# 03_Breakout_Headers.net
KiCad netlist of a schematic drawn in Altium Designer
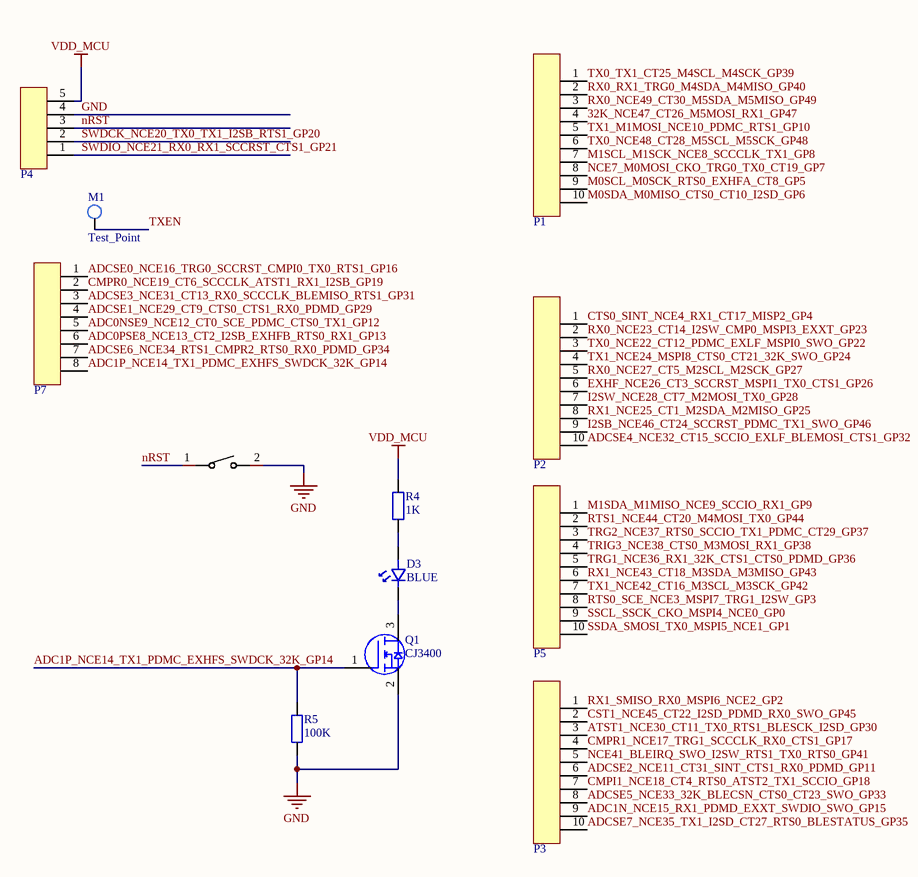
[diagram p0: [03]Breakout Headers.SchDoc]

(export (version "E")
  (design (tool "Eeschema 10.0.6"))
  (components
    (comp (ref "D3")
      (value "BLUE")
      (footprint "LEDC1608L")
      (description "Surface Mount LED")
      (libsource (lib "Discrete") (part "LED_SMD"))
    )
    (comp (ref "M1")
      (value "Test_Point")
      (footprint "MARK_Small")
      (libsource (lib "AmbiqPhoenix") (part "Test_Point_Small"))
    )
    (comp (ref "P1")
      (value "Header 1X10")
      (footprint "HEADER1X10")
      (libsource (lib "AmbiqPhoenix") (part "HDR1X10"))
    )
    (comp (ref "P2")
      (value "Header 1X10")
      (footprint "HEADER1X10")
      (libsource (lib "AmbiqPhoenix") (part "HDR1X10"))
    )
    (comp (ref "P3")
      (value "Header 1X10")
      (footprint "HEADER1X10")
      (libsource (lib "AmbiqPhoenix") (part "HDR1X10"))
    )
    (comp (ref "P4")
      (value "Header 1X8")
      (footprint "HEADER1X5")
      (libsource (lib "AmbiqPhoenix") (part "HDR1X5"))
    )
    (comp (ref "P5")
      (value "Header 1X10")
      (footprint "HEADER1X10")
      (libsource (lib "AmbiqPhoenix") (part "HDR1X10"))
    )
    (comp (ref "P7")
      (value "Header 1X8")
      (footprint "HEADER1X8")
      (libsource (lib "AmbiqPhoenix") (part "HDR1X8"))
    )
    (comp (ref "Q1")
      (value "CJ3400")
      (footprint "SOT23-3L")
      (description "N-Channel MOSFET")
      (libsource (lib "AmbiqPhoenix") (part "MOS_N"))
    )
    (comp (ref "R4")
      (value "1K")
      (footprint "RESC1005L")
      (description "Surface Mount Resistor")
      (libsource (lib "Discrete") (part "RES_CHP"))
    )
    (comp (ref "R5")
      (value "100K")
      (footprint "RESC1005L")
      (description "Surface Mount Resistor")
      (libsource (lib "Discrete") (part "RES_CHP"))
    )
    (comp (ref "SW1")
      (value "TS-1088-AR02016")
      (footprint "SW-SMD_L4.0-W2.9-LS5.0")
      (fields (field (name "MANUFACTURER") "XUNPU(讯普)"))
      (libsource (lib "AmbiqPhoenix") (part "TS-1088-AR02016"))
    )
  )
  (nets
    (net (code "1") (name "/32K_NCE47_CT26_M5MOSI_RX1_GP47") (class "Default")
      (node (ref "P1") (pin "4") (pinfunction "4_4") (pintype "passive"))
    )
    (net (code "2") (name "/ADC0NSE9_NCE12_CT0_SCE_PDMC_CTS0_TX1_GP12") (class "Default")
      (node (ref "P7") (pin "5") (pinfunction "5_5") (pintype "passive"))
    )
    (net (code "3") (name "/ADC0PSE8_NCE13_CT2_I2SB_EXHFB_RTS0_RX1_GP13") (class "Default")
      (node (ref "P7") (pin "6") (pinfunction "6_6") (pintype "passive"))
    )
    (net (code "4") (name "/ADC1N_NCE15_RX1_PDMD_EXXT_SWDIO_SWO_GP15") (class "Default")
      (node (ref "P3") (pin "9") (pinfunction "9_9") (pintype "passive"))
    )
    (net (code "5") (name "/ADC1P_NCE14_TX1_PDMC_EXHFS_SWDCK_32K_GP14") (class "Default")
      (node (ref "P7") (pin "8") (pinfunction "8_8") (pintype "passive"))
      (node (ref "Q1") (pin "1") (pinfunction "1_1") (pintype "passive"))
      (node (ref "R5") (pin "2") (pinfunction "2_2") (pintype "passive"))
    )
    (net (code "6") (name "/ADCSE0_NCE16_TRG0_SCCRST_CMPI0_TX0_RTS1_GP16") (class "Default")
      (node (ref "P7") (pin "1") (pinfunction "1_1") (pintype "passive"))
    )
    (net (code "7") (name "/ADCSE1_NCE29_CT9_CTS0_CTS1_RX0_PDMD_GP29") (class "Default")
      (node (ref "P7") (pin "4") (pinfunction "4_4") (pintype "passive"))
    )
    (net (code "8") (name "/ADCSE2_NCE11_CT31_SINT_CTS1_RX0_PDMD_GP11") (class "Default")
      (node (ref "P3") (pin "6") (pinfunction "6_6") (pintype "passive"))
    )
    (net (code "9") (name "/ADCSE3_NCE31_CT13_RX0_SCCCLK_BLEMISO_RTS1_GP31") (class "Default")
      (node (ref "P7") (pin "3") (pinfunction "3_3") (pintype "passive"))
    )
    (net (code "10") (name "/ADCSE4_NCE32_CT15_SCCIO_EXLF_BLEMOSI_CTS1_GP32") (class "Default")
      (node (ref "P2") (pin "10") (pinfunction "10_10") (pintype "passive"))
    )
    (net (code "11") (name "/ADCSE5_NCE33_32K_BLECSN_CTS0_CT23_SWO_GP33") (class "Default")
      (node (ref "P3") (pin "8") (pinfunction "8_8") (pintype "passive"))
    )
    (net (code "12") (name "/ADCSE6_NCE34_RTS1_CMPR2_RTS0_RX0_PDMD_GP34") (class "Default")
      (node (ref "P7") (pin "7") (pinfunction "7_7") (pintype "passive"))
    )
    (net (code "13") (name "/ADCSE7_NCE35_TX1_I2SD_CT27_RTS0_BLESTATUS_GP35") (class "Default")
      (node (ref "P3") (pin "10") (pinfunction "10_10") (pintype "passive"))
    )
    (net (code "14") (name "/ATST1_NCE30_CT11_TX0_RTS1_BLESCK_I2SD_GP30") (class "Default")
      (node (ref "P3") (pin "3") (pinfunction "3_3") (pintype "passive"))
    )
    (net (code "15") (name "/CMPI1_NCE18_CT4_RTS0_ATST2_TX1_SCCIO_GP18") (class "Default")
      (node (ref "P3") (pin "7") (pinfunction "7_7") (pintype "passive"))
    )
    (net (code "16") (name "/CMPR0_NCE19_CT6_SCCCLK_ATST1_RX1_I2SB_GP19") (class "Default")
      (node (ref "P7") (pin "2") (pinfunction "2_2") (pintype "passive"))
    )
    (net (code "17") (name "/CMPR1_NCE17_TRG1_SCCCLK_RX0_CTS1_GP17") (class "Default")
      (node (ref "P3") (pin "4") (pinfunction "4_4") (pintype "passive"))
    )
    (net (code "18") (name "/CST1_NCE45_CT22_I2SD_PDMD_RX0_SWO_GP45") (class "Default")
      (node (ref "P3") (pin "2") (pinfunction "2_2") (pintype "passive"))
    )
    (net (code "19") (name "/CTS0_SINT_NCE4_RX1_CT17_MISP2_GP4") (class "Default")
      (node (ref "P2") (pin "1") (pinfunction "1_1") (pintype "passive"))
    )
    (net (code "20") (name "/EXHF_NCE26_CT3_SCCRST_MSPI1_TX0_CTS1_GP26") (class "Default")
      (node (ref "P2") (pin "6") (pinfunction "6_6") (pintype "passive"))
    )
    (net (code "21") (name "/I2SB_NCE46_CT24_SCCRST_PDMC_TX1_SWO_GP46") (class "Default")
      (node (ref "P2") (pin "9") (pinfunction "9_9") (pintype "passive"))
    )
    (net (code "22") (name "/I2SW_NCE28_CT7_M2MOSI_TX0_GP28") (class "Default")
      (node (ref "P2") (pin "7") (pinfunction "7_7") (pintype "passive"))
    )
    (net (code "23") (name "/M0SCL_M0SCK_RTS0_EXHFA_CT8_GP5") (class "Default")
      (node (ref "P1") (pin "9") (pinfunction "9_9") (pintype "passive"))
    )
    (net (code "24") (name "/M0SDA_M0MISO_CTS0_CT10_I2SD_GP6") (class "Default")
      (node (ref "P1") (pin "10") (pinfunction "10_10") (pintype "passive"))
    )
    (net (code "25") (name "/M1SCL_M1SCK_NCE8_SCCCLK_TX1_GP8") (class "Default")
      (node (ref "P1") (pin "7") (pinfunction "7_7") (pintype "passive"))
    )
    (net (code "26") (name "/M1SDA_M1MISO_NCE9_SCCIO_RX1_GP9") (class "Default")
      (node (ref "P5") (pin "1") (pinfunction "1_1") (pintype "passive"))
    )
    (net (code "27") (name "/NCE7_M0MOSI_CKO_TRG0_TX0_CT19_GP7") (class "Default")
      (node (ref "P1") (pin "8") (pinfunction "8_8") (pintype "passive"))
    )
    (net (code "28") (name "/NCE41_BLEIRQ_SWO_I2SW_RTS1_TX0_RTS0_GP41") (class "Default")
      (node (ref "P3") (pin "5") (pinfunction "5_5") (pintype "passive"))
    )
    (net (code "29") (name "/RTS0_SCE_NCE3_MSPI7_TRG1_I2SW_GP3") (class "Default")
      (node (ref "P5") (pin "8") (pinfunction "8_8") (pintype "passive"))
    )
    (net (code "30") (name "/RTS1_NCE44_CT20_M4MOSI_TX0_GP44") (class "Default")
      (node (ref "P5") (pin "2") (pinfunction "2_2") (pintype "passive"))
    )
    (net (code "31") (name "/RX0_NCE23_CT14_I2SW_CMP0_MSPI3_EXXT_GP23") (class "Default")
      (node (ref "P2") (pin "2") (pinfunction "2_2") (pintype "passive"))
    )
    (net (code "32") (name "/RX0_NCE27_CT5_M2SCL_M2SCK_GP27") (class "Default")
      (node (ref "P2") (pin "5") (pinfunction "5_5") (pintype "passive"))
    )
    (net (code "33") (name "/RX0_NCE49_CT30_M5SDA_M5MISO_GP49") (class "Default")
      (node (ref "P1") (pin "3") (pinfunction "3_3") (pintype "passive"))
    )
    (net (code "34") (name "/RX0_RX1_TRG0_M4SDA_M4MISO_GP40") (class "Default")
      (node (ref "P1") (pin "2") (pinfunction "2_2") (pintype "passive"))
    )
    (net (code "35") (name "/RX1_NCE25_CT1_M2SDA_M2MISO_GP25") (class "Default")
      (node (ref "P2") (pin "8") (pinfunction "8_8") (pintype "passive"))
    )
    (net (code "36") (name "/RX1_NCE43_CT18_M3SDA_M3MISO_GP43") (class "Default")
      (node (ref "P5") (pin "6") (pinfunction "6_6") (pintype "passive"))
    )
    (net (code "37") (name "/RX1_SMISO_RX0_MSPI6_NCE2_GP2") (class "Default")
      (node (ref "P3") (pin "1") (pinfunction "1_1") (pintype "passive"))
    )
    (net (code "38") (name "/SSCL_SSCK_CKO_MSPI4_NCE0_GP0") (class "Default")
      (node (ref "P5") (pin "9") (pinfunction "9_9") (pintype "passive"))
    )
    (net (code "39") (name "/SSDA_SMOSI_TX0_MSPI5_NCE1_GP1") (class "Default")
      (node (ref "P5") (pin "10") (pinfunction "10_10") (pintype "passive"))
    )
    (net (code "40") (name "/SWDCK_NCE20_TX0_TX1_I2SB_RTS1_GP20") (class "Default")
      (node (ref "P4") (pin "2") (pinfunction "2_2") (pintype "passive"))
    )
    (net (code "41") (name "/SWDIO_NCE21_RX0_RX1_SCCRST_CTS1_GP21") (class "Default")
      (node (ref "P4") (pin "1") (pinfunction "1_1") (pintype "passive"))
    )
    (net (code "42") (name "/TRG1_NCE36_RX1_32K_CTS1_CTS0_PDMD_GP36") (class "Default")
      (node (ref "P5") (pin "5") (pinfunction "5_5") (pintype "passive"))
    )
    (net (code "43") (name "/TRG2_NCE37_RTS0_SCCIO_TX1_PDMC_CT29_GP37") (class "Default")
      (node (ref "P5") (pin "3") (pinfunction "3_3") (pintype "passive"))
    )
    (net (code "44") (name "/TRIG3_NCE38_CTS0_M3MOSI_RX1_GP38") (class "Default")
      (node (ref "P5") (pin "4") (pinfunction "4_4") (pintype "passive"))
    )
    (net (code "45") (name "/TX0_NCE22_CT12_PDMC_EXLF_MSPI0_SWO_GP22") (class "Default")
      (node (ref "P2") (pin "3") (pinfunction "3_3") (pintype "passive"))
    )
    (net (code "46") (name "/TX0_NCE48_CT28_M5SCL_M5SCK_GP48") (class "Default")
      (node (ref "P1") (pin "6") (pinfunction "6_6") (pintype "passive"))
    )
    (net (code "47") (name "/TX0_TX1_CT25_M4SCL_M4SCK_GP39") (class "Default")
      (node (ref "P1") (pin "1") (pinfunction "1_1") (pintype "passive"))
    )
    (net (code "48") (name "/TX1_M1MOSI_NCE10_PDMC_RTS1_GP10") (class "Default")
      (node (ref "P1") (pin "5") (pinfunction "5_5") (pintype "passive"))
    )
    (net (code "49") (name "/TX1_NCE24_MSPI8_CTS0_CT21_32K_SWO_GP24") (class "Default")
      (node (ref "P2") (pin "4") (pinfunction "4_4") (pintype "passive"))
    )
    (net (code "50") (name "/TX1_NCE42_CT16_M3SCL_M3SCK_GP42") (class "Default")
      (node (ref "P5") (pin "7") (pinfunction "7_7") (pintype "passive"))
    )
    (net (code "51") (name "/TXEN") (class "Default")
      (node (ref "M1") (pin "1") (pinfunction "1_1") (pintype "passive"))
    )
    (net (code "52") (name "/nRST") (class "Default")
      (node (ref "P4") (pin "3") (pinfunction "3_3") (pintype "passive"))
      (node (ref "SW1") (pin "1") (pinfunction "1_1") (pintype "passive"))
    )
    (net (code "53") (name "GND") (class "Default")
      (node (ref "P4") (pin "4") (pinfunction "4_4") (pintype "passive"))
      (node (ref "Q1") (pin "2") (pinfunction "2_2") (pintype "passive"))
      (node (ref "R5") (pin "1") (pinfunction "1_1") (pintype "passive"))
      (node (ref "SW1") (pin "2") (pinfunction "2_2") (pintype "passive"))
    )
    (net (code "54") (name "Net-(D3-Pad1)") (class "Default")
      (node (ref "D3") (pin "1") (pinfunction "1_1") (pintype "passive"))
      (node (ref "Q1") (pin "3") (pinfunction "3_3") (pintype "passive"))
    )
    (net (code "55") (name "Net-(D3-Pad2)") (class "Default")
      (node (ref "D3") (pin "2") (pinfunction "2_2") (pintype "passive"))
      (node (ref "R4") (pin "1") (pinfunction "1_1") (pintype "passive"))
    )
    (net (code "56") (name "VDD_MCU") (class "Default")
      (node (ref "P4") (pin "5") (pinfunction "5_5") (pintype "passive"))
      (node (ref "R4") (pin "2") (pinfunction "2_2") (pintype "passive"))
    )
  )
)
